# Sheet1.net
KiCad netlist of a schematic drawn in Altium Designer
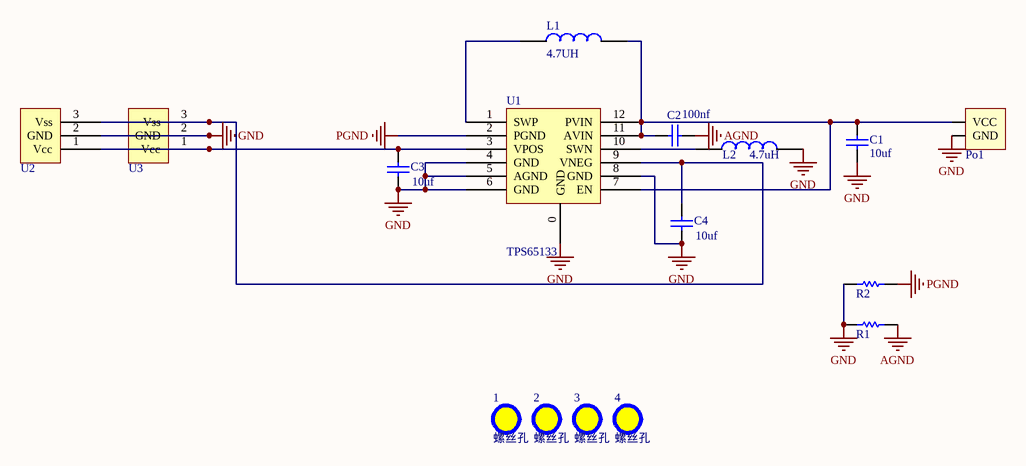
[diagram p0: Sheet1.SchDoc]

(export (version "E")
  (design (tool "Eeschema 10.0.6"))
  (components
    (comp (ref "1") (value "螺丝孔") (footprint "固定过孔") (libsource (lib "Schlib1") (part "螺丝孔")))
    (comp (ref "2") (value "螺丝孔") (footprint "固定过孔") (libsource (lib "Schlib1") (part "螺丝孔")))
    (comp (ref "3") (value "螺丝孔") (footprint "固定过孔") (libsource (lib "Schlib1") (part "螺丝孔")))
    (comp (ref "4") (value "螺丝孔") (footprint "固定过孔") (libsource (lib "Schlib1") (part "螺丝孔")))
    (comp (ref "C1")
      (value "Cap1")
      (footprint "0805")
      (fields (field (name "值") "10uf"))
      (libsource (lib "Schlib1") (part "Cap1"))
    )
    (comp (ref "C2")
      (value "Cap1")
      (footprint "0805")
      (fields (field (name "值") "100nf"))
      (libsource (lib "Schlib1") (part "Cap1"))
    )
    (comp (ref "C3")
      (value "Cap1")
      (footprint "0805")
      (fields (field (name "值") "10uf"))
      (libsource (lib "Schlib1") (part "Cap1"))
    )
    (comp (ref "C4")
      (value "Cap1")
      (footprint "0805")
      (fields (field (name "值") "10uf"))
      (libsource (lib "Schlib1") (part "Cap1"))
    )
    (comp (ref "L1") (value "4.7UH") (footprint "2520") (libsource (lib "Schlib1") (part "IND DFE252012C")))
    (comp (ref "L2") (value "4.7uH") (footprint "2520") (libsource (lib "Schlib1") (part "IND DFE252012C")))
    (comp (ref "Po1")
      (value "Power_2Port")
      (footprint "Power_S_2Port")
      (libsource (lib "Schlib1") (part "Power_2Port"))
    )
    (comp (ref "R1") (value "RES") (footprint "0805") (libsource (lib "Schlib1") (part "RES")))
    (comp (ref "R2") (value "RES") (footprint "0805") (libsource (lib "Schlib1") (part "RES")))
    (comp (ref "U1")
      (value "TPS65133")
      (footprint "QFN-12 3X3")
      (libsource (lib "Schlib1") (part "TPS65133"))
    )
    (comp (ref "U2")
      (value "XH2.54-3p")
      (footprint "XH2.54-3p")
      (libsource (lib "Schlib1") (part "XH2.54-3p"))
    )
    (comp (ref "U3")
      (value "XH2.54-3p")
      (footprint "XH2.54-3p")
      (libsource (lib "Schlib1") (part "XH2.54-3p"))
    )
  )
  (nets
    (net (code "1") (name "AGND") (class "Default")
      (node (ref "C2") (pin "1") (pinfunction "1_1") (pintype "passive"))
      (node (ref "R1") (pin "2") (pinfunction "2_2") (pintype "passive"))
    )
    (net (code "2") (name "GND") (class "Default")
      (node (ref "C1") (pin "1") (pinfunction "1_1") (pintype "passive"))
      (node (ref "C3") (pin "1") (pinfunction "1_1") (pintype "passive"))
      (node (ref "C4") (pin "1") (pinfunction "1_1") (pintype "passive"))
      (node (ref "L2") (pin "2") (pintype "passive"))
      (node (ref "Po1") (pin "2") (pinfunction "GND_2") (pintype "passive"))
      (node (ref "R1") (pin "1") (pinfunction "1_1") (pintype "passive"))
      (node (ref "R2") (pin "1") (pinfunction "1_1") (pintype "passive"))
      (node (ref "U1") (pin "0") (pinfunction "GND_0") (pintype "passive"))
      (node (ref "U1") (pin "4") (pinfunction "GND_4") (pintype "passive"))
      (node (ref "U1") (pin "5") (pinfunction "AGND_5") (pintype "passive"))
      (node (ref "U1") (pin "6") (pinfunction "GND_6") (pintype "passive"))
      (node (ref "U1") (pin "8") (pinfunction "GND_8") (pintype "passive"))
      (node (ref "U2") (pin "2") (pinfunction "GND_2") (pintype "passive"))
      (node (ref "U3") (pin "2") (pinfunction "GND_2") (pintype "passive"))
    )
    (net (code "3") (name "Net-(Po1-VCC)") (class "Default")
      (node (ref "C1") (pin "2") (pinfunction "2_2") (pintype "passive"))
      (node (ref "C2") (pin "2") (pinfunction "2_2") (pintype "passive"))
      (node (ref "L1") (pin "2") (pintype "passive"))
      (node (ref "Po1") (pin "1") (pinfunction "VCC_1") (pintype "passive"))
      (node (ref "U1") (pin "11") (pinfunction "AVIN_11") (pintype "passive"))
      (node (ref "U1") (pin "12") (pinfunction "PVIN_12") (pintype "passive"))
      (node (ref "U1") (pin "7") (pinfunction "EN_7") (pintype "passive"))
    )
    (net (code "4") (name "Net-(U1-SWN)") (class "Default")
      (node (ref "L2") (pin "1") (pintype "passive"))
      (node (ref "U1") (pin "10") (pinfunction "SWN_10") (pintype "passive"))
    )
    (net (code "5") (name "Net-(U1-SWP)") (class "Default")
      (node (ref "L1") (pin "1") (pintype "passive"))
      (node (ref "U1") (pin "1") (pinfunction "SWP_1") (pintype "passive"))
    )
    (net (code "6") (name "Net-(U1-VNEG)") (class "Default")
      (node (ref "C4") (pin "2") (pinfunction "2_2") (pintype "passive"))
      (node (ref "U1") (pin "9") (pinfunction "VNEG_9") (pintype "passive"))
      (node (ref "U2") (pin "3") (pinfunction "Vss_3") (pintype "passive"))
      (node (ref "U3") (pin "3") (pinfunction "Vss_3") (pintype "passive"))
    )
    (net (code "7") (name "Net-(U1-VPOS)") (class "Default")
      (node (ref "C3") (pin "2") (pinfunction "2_2") (pintype "passive"))
      (node (ref "U1") (pin "3") (pinfunction "VPOS_3") (pintype "passive"))
      (node (ref "U2") (pin "1") (pinfunction "Vcc_1") (pintype "passive"))
      (node (ref "U3") (pin "1") (pinfunction "Vcc_1") (pintype "passive"))
    )
    (net (code "8") (name "PGND") (class "Default")
      (node (ref "R2") (pin "2") (pinfunction "2_2") (pintype "passive"))
      (node (ref "U1") (pin "2") (pinfunction "PGND_2") (pintype "passive"))
    )
  )
)
